# board1.net
KiCad netlist of a schematic drawn in Altium Designer
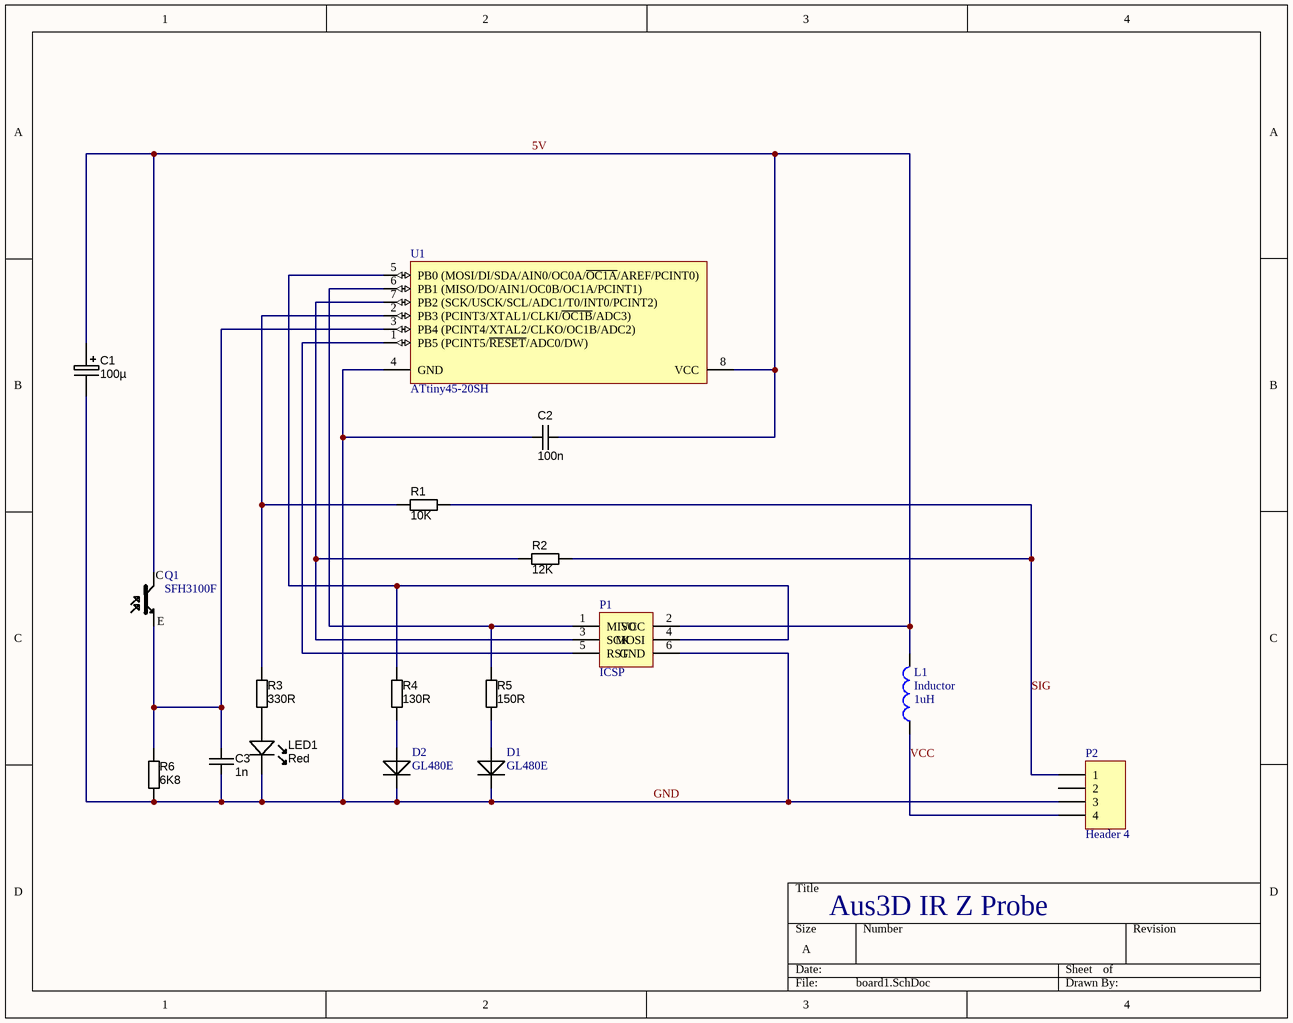
[diagram p0: board1.SchDoc]

(export (version "E")
  (design (tool "Eeschema 10.0.6"))
  (components
    (comp (ref "C1")
      (value "100µ")
      (footprint "6.3-DIA-CAP")
      (description "Capacitor THD Electrolytic 100uF 20% 16V Radial")
      (fields (field (name "TOLERANCE") "±20%") (field (name "MANUFACTURER") "Panasonic - ECG"))
      (libsource (lib "PBL - Capacitors") (part "CAPE_100u_16V_THD"))
    )
    (comp (ref "C2")
      (value "100n")
      (footprint "CAPC1005X55N")
      (description "Capacitor SMD Cer 100nF 10% 16V X5R 0402")
      (fields (field (name "TOLERANCE") "±10%"))
      (libsource (lib "PBL - Capacitors") (part "CAPC_100n_0402_X5R_16V_10%"))
    )
    (comp (ref "C3")
      (value "1n")
      (footprint "CAPC1005X55N")
      (description "Capacitor SMD Cer 1nF 10% 16V X7R 0402")
      (fields (field (name "TOLERANCE") "±10%"))
      (libsource (lib "PBL - Capacitors") (part "CAPC_1n_0402_X7R_16V_10%"))
    )
    (comp (ref "D1")
      (value "GL480E")
      (footprint "LED-2.54spacing")
      (libsource (lib "Schlib1") (part "GL480E"))
    )
    (comp (ref "D2")
      (value "GL480E")
      (footprint "LED-2.54spacing")
      (libsource (lib "Schlib1") (part "GL480E"))
    )
    (comp (ref "L1")
      (value "Inductor")
      (footprint "INDC1608L")
      (fields (field (name "ALTIUM_VALUE") "1uH") (field (name "PUBLISHER") "Altium Limited"))
      (libsource (lib "Miscellaneous Devices") (part "Inductor"))
    )
    (comp (ref "LED1")
      (value "Red")
      (footprint "LED-0603-RED")
      (description "LED 0603 SMD Hyper Red 630nm 220mcd 20mA")
      (libsource (lib "PBL - Light Sources") (part "LED_SMD_Red_0603_220mcd"))
    )
    (comp (ref "P1")
      (value "ICSP")
      (footprint "HDR2X3")
      (description "Header, 3-Pin, Dual row")
      (fields (field (name "PUBLISHER") "Altium Limited"))
      (libsource (lib "Miscellaneous Connectors") (part "Header 3X2"))
    )
    (comp (ref "P2")
      (value "Header 4")
      (footprint "HDR1X4")
      (description "Header, 4-Pin")
      (fields (field (name "PUBLISHER") "Altium Limited"))
      (libsource (lib "Miscellaneous Connectors") (part "Header 4"))
    )
    (comp (ref "Q1")
      (value "SFH3100F")
      (footprint "SFH3100F-footprint")
      (description "GL480E")
      (libsource (lib "Schlib1") (part "SFH3100F"))
    )
    (comp (ref "R1")
      (value "10K")
      (footprint "RESC1608X55N")
      (description "Resistor SMD chip 2.2k Ohm 0.1W 5% 0603")
      (fields (field (name "TOLERANCE") "±5%") (field (name "Comment") "Thick Film"))
      (libsource (lib "PBL - Resistors") (part "RES_2K2_0603_5%"))
    )
    (comp (ref "R2")
      (value "12K")
      (footprint "RESC1608X55N")
      (description "Resistor SMD chip 2.2k Ohm 0.1W 5% 0603")
      (fields (field (name "TOLERANCE") "±5%") (field (name "Comment") "Thick Film"))
      (libsource (lib "PBL - Resistors") (part "RES_2K2_0603_5%"))
    )
    (comp (ref "R3")
      (value "330R")
      (footprint "RESC1608X55N")
      (description "Resistor SMD chip 330 Ohm 0.1W 5% 0603")
      (fields (field (name "TOLERANCE") "±5%") (field (name "Comment") "Thick Film"))
      (libsource (lib "PBL - Resistors") (part "RES_330R_0603_5%"))
    )
    (comp (ref "R4")
      (value "130R")
      (footprint "RESC1608X55N")
      (description "Resistor SMD chip 2.2k Ohm 0.1W 5% 0603")
      (fields (field (name "TOLERANCE") "±5%") (field (name "Comment") "Thick Film"))
      (libsource (lib "") (part "RES_2K2_0603_5%_1"))
    )
    (comp (ref "R5")
      (value "150R")
      (footprint "RESC1608X55N")
      (description "Resistor SMD chip 2.2k Ohm 0.1W 5% 0603")
      (fields (field (name "TOLERANCE") "±5%") (field (name "Comment") "Thick Film"))
      (libsource (lib "") (part "RES_2K2_0603_5%_1"))
    )
    (comp (ref "R6")
      (value "6K8")
      (footprint "RESC1608X55N")
      (description "Resistor SMD chip 2.2k Ohm 0.1W 5% 0603")
      (fields (field (name "TOLERANCE") "±5%") (field (name "Comment") "Thick Film"))
      (libsource (lib "") (part "RES_2K2_0603_5%_1"))
    )
    (comp (ref "U1")
      (value "ATtiny45-20SH")
      (footprint "8S2_N")
      (libsource (lib "Atmel Microcontroller tinyAVR") (part "ATtiny45-20SH"))
    )
  )
  (nets
    (net (code "1") (name "/5V") (class "Default")
      (node (ref "C1") (pin "1") (pintype "passive"))
      (node (ref "C2") (pin "2") (pintype "passive"))
      (node (ref "L1") (pin "2") (pinfunction "2_2") (pintype "passive"))
      (node (ref "P1") (pin "2") (pinfunction "VCC_2") (pintype "passive"))
      (node (ref "Q1") (pin "1") (pinfunction "1_1") (pintype "passive"))
      (node (ref "U1") (pin "8") (pinfunction "VCC_8") (pintype "power_in"))
    )
    (net (code "2") (name "/GND") (class "Default")
      (node (ref "C1") (pin "2") (pintype "passive"))
      (node (ref "C2") (pin "1") (pintype "passive"))
      (node (ref "C3") (pin "2") (pintype "passive"))
      (node (ref "D1") (pin "1") (pinfunction "1_1") (pintype "passive"))
      (node (ref "D2") (pin "1") (pinfunction "1_1") (pintype "passive"))
      (node (ref "LED1") (pin "K") (pinfunction "K_K") (pintype "passive"))
      (node (ref "P1") (pin "6") (pinfunction "GND_6") (pintype "passive"))
      (node (ref "P2") (pin "3") (pinfunction "3_3") (pintype "passive"))
      (node (ref "R6") (pin "1") (pinfunction "1_1") (pintype "passive"))
      (node (ref "U1") (pin "4") (pinfunction "GND_4") (pintype "power_in"))
    )
    (net (code "3") (name "/SIG") (class "Default")
      (node (ref "P2") (pin "1") (pinfunction "1_1") (pintype "passive"))
      (node (ref "R1") (pin "1") (pinfunction "1_1") (pintype "passive"))
      (node (ref "R2") (pin "1") (pinfunction "1_1") (pintype "passive"))
    )
    (net (code "4") (name "/VCC") (class "Default")
      (node (ref "L1") (pin "1") (pinfunction "1_1") (pintype "passive"))
      (node (ref "P2") (pin "4") (pinfunction "4_4") (pintype "passive"))
    )
    (net (code "5") (name "Net-(D1-Pad2)") (class "Default")
      (node (ref "D1") (pin "2") (pinfunction "2_2") (pintype "passive"))
      (node (ref "R5") (pin "1") (pinfunction "1_1") (pintype "passive"))
    )
    (net (code "6") (name "Net-(D2-Pad2)") (class "Default")
      (node (ref "D2") (pin "2") (pinfunction "2_2") (pintype "passive"))
      (node (ref "R4") (pin "1") (pinfunction "1_1") (pintype "passive"))
    )
    (net (code "7") (name "Net-(LED1-PadA)") (class "Default")
      (node (ref "LED1") (pin "A") (pinfunction "A_A") (pintype "passive"))
      (node (ref "R3") (pin "2") (pinfunction "2_2") (pintype "passive"))
    )
    (net (code "8") (name "Net-(P1-MISO)") (class "Default")
      (node (ref "P1") (pin "1") (pinfunction "MISO_1") (pintype "passive"))
      (node (ref "R5") (pin "2") (pinfunction "2_2") (pintype "passive"))
      (node (ref "U1") (pin "6") (pinfunction "PB1_(MISO/DO/AIN1/OC0B/OC1A/PCINT1)_6") (pintype "bidirectional"))
    )
    (net (code "9") (name "Net-(P1-MOSI)") (class "Default")
      (node (ref "P1") (pin "4") (pinfunction "MOSI_4") (pintype "passive"))
      (node (ref "R4") (pin "2") (pinfunction "2_2") (pintype "passive"))
      (node (ref "U1") (pin "5") (pinfunction "PB0_(MOSI/DI/SDA/AIN0/OC0A/~{OC1A}/AREF/PCINT0)_5") (pintype "bidirectional"))
    )
    (net (code "10") (name "Net-(P1-RST)") (class "Default")
      (node (ref "P1") (pin "5") (pinfunction "RST_5") (pintype "passive"))
      (node (ref "U1") (pin "1") (pinfunction "PB5_(PCINT5/~{RESET}/ADC0/DW)_1") (pintype "bidirectional"))
    )
    (net (code "11") (name "Net-(P1-SCK)") (class "Default")
      (node (ref "P1") (pin "3") (pinfunction "SCK_3") (pintype "passive"))
      (node (ref "R2") (pin "2") (pinfunction "2_2") (pintype "passive"))
      (node (ref "U1") (pin "7") (pinfunction "PB2_(SCK/USCK/SCL/ADC1/T0/INT0/PCINT2)_7") (pintype "bidirectional"))
    )
    (net (code "12") (name "Net-(U1-PB3_(PCINT3{slash}XTAL1{slash}CLKI{slash}~{OC1B}{slash}ADC3))") (class "Default")
      (node (ref "R1") (pin "2") (pinfunction "2_2") (pintype "passive"))
      (node (ref "R3") (pin "1") (pinfunction "1_1") (pintype "passive"))
      (node (ref "U1") (pin "2") (pinfunction "PB3_(PCINT3/XTAL1/CLKI/~{OC1B}/ADC3)_2") (pintype "bidirectional"))
    )
    (net (code "13") (name "Net-(U1-PB4_(PCINT4{slash}XTAL2{slash}CLKO{slash}OC1B{slash}ADC2))") (class "Default")
      (node (ref "C3") (pin "1") (pintype "passive"))
      (node (ref "Q1") (pin "2") (pinfunction "2_2") (pintype "passive"))
      (node (ref "R6") (pin "2") (pinfunction "2_2") (pintype "passive"))
      (node (ref "U1") (pin "3") (pinfunction "PB4_(PCINT4/XTAL2/CLKO/OC1B/ADC2)_3") (pintype "bidirectional"))
    )
    (net (code "14") (name "unconnected-(P2-Pad2)") (class "Default")
      (node (ref "P2") (pin "2") (pinfunction "2_2") (pintype "passive"))
    )
  )
)
